# PANEL_A3_v4.net
KiCad netlist of a schematic drawn in Altium Designer
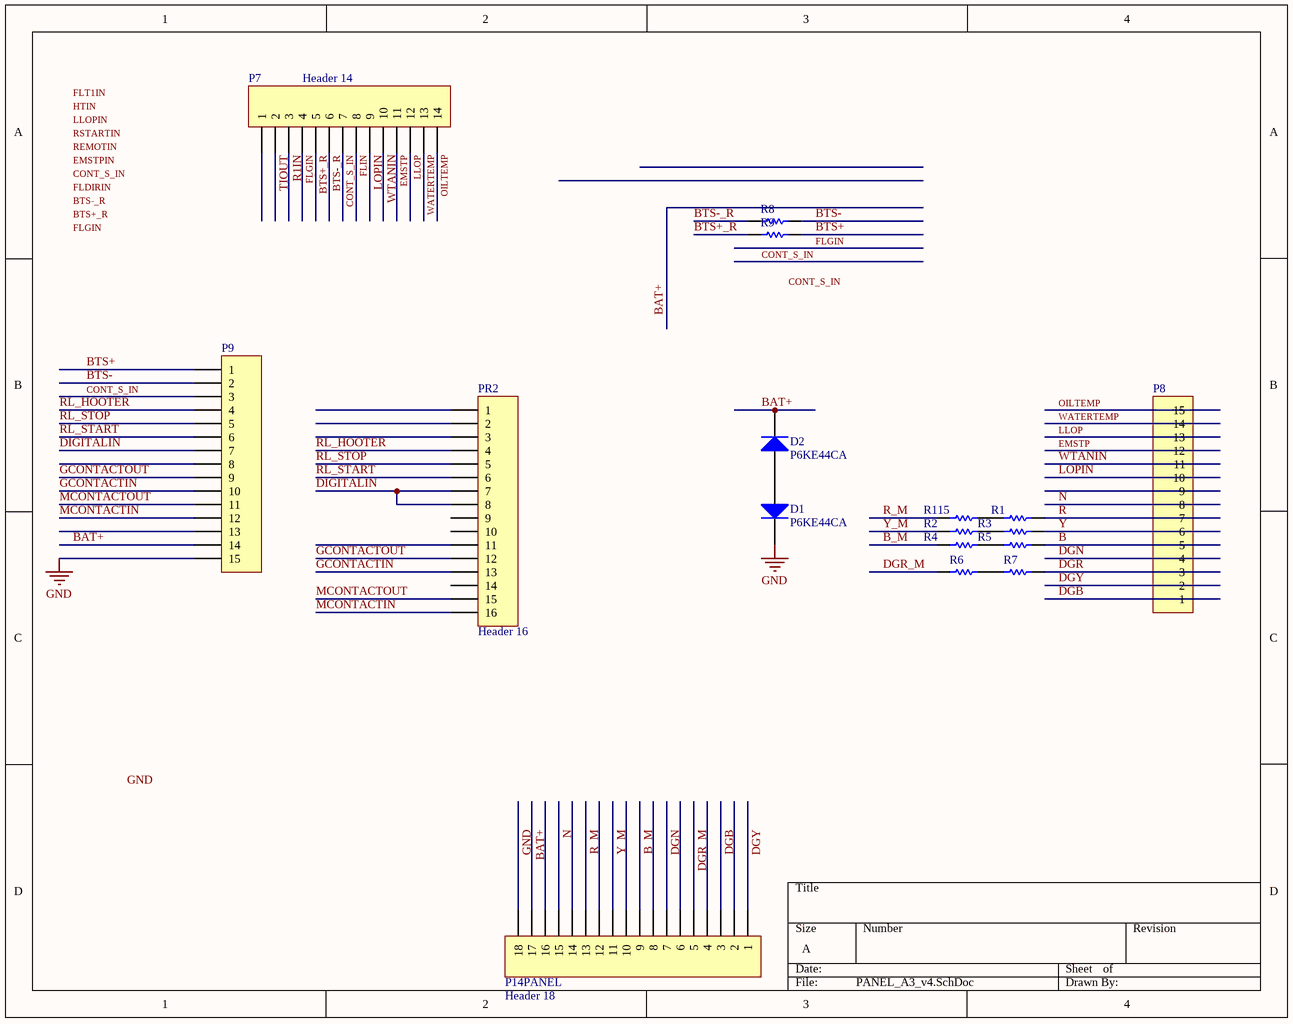
[diagram p0: PANEL_A3_v4.SchDoc]

(export (version "E")
  (design (tool "Eeschema 10.0.6"))
  (components
    (comp (ref "D1")
      (value "P6KE44CA")
      (footprint "DIODE1A")
      (description "3 Amp Medium Power Silicon Rectifier Diode")
      (fields (field (name "PUBLISHER") "Altium Limited"))
      (libsource (lib "Miscellaneous Devices") (part "Diode 1N5408"))
    )
    (comp (ref "D2")
      (value "P6KE44CA")
      (footprint "DIODE1A")
      (description "3 Amp Medium Power Silicon Rectifier Diode")
      (fields (field (name "PUBLISHER") "Altium Limited"))
      (libsource (lib "Miscellaneous Devices") (part "Diode 1N5408"))
    )
    (comp (ref "P7")
      (value "Header 14")
      (footprint "HDR1X14_BURGE_M")
      (description "Header, 14-Pin")
      (fields (field (name "PUBLISHER") "Altium Limited"))
      (libsource (lib "Miscellaneous Connectors") (part "Header 14"))
    )
    (comp (ref "P8")
      (value "XY2500 7PIN+8PIN MALE ST, FEMALE R/A")
      (footprint "XY2500_15PIN_M_ST")
      (description "Header, 15-Pin")
      (fields (field (name "PUBLISHER") "Altium Limited"))
      (libsource (lib "") (part "Header 15_1"))
    )
    (comp (ref "P9")
      (value "XY2500 7PIN+8PIN MALE ST, FEMALE R/A")
      (footprint "XY2500_15PIN_M_ST")
      (description "Header, 15-Pin")
      (fields (field (name "PUBLISHER") "Altium Limited"))
      (libsource (lib "Miscellaneous Connectors") (part "Header 15"))
    )
    (comp (ref "P14PANEL")
      (value "Header 18")
      (footprint "HDR1X18_BURGE_M")
      (description "Header, 18-Pin")
      (fields (field (name "PUBLISHER") "Altium Limited"))
      (libsource (lib "Miscellaneous Connectors") (part "Header 18"))
    )
    (comp (ref "PR2")
      (value "Header 16")
      (footprint "HDR1X16_BURGE_F")
      (description "Header, 16-Pin")
      (fields (field (name "PUBLISHER") "Altium Limited"))
      (libsource (lib "Miscellaneous Connectors") (part "Header 16"))
    )
    (comp (ref "R1")
      (value "MFR 1M .5W")
      (footprint "AXIAL-0.5")
      (description "Semiconductor Resistor")
      (fields (field (name "PUBLISHER") "Altium Limited"))
      (libsource (lib "Miscellaneous Devices") (part "Res Semi"))
    )
    (comp (ref "R2")
      (value "MFR 1M .5W")
      (footprint "AXIAL-0.5")
      (description "Semiconductor Resistor")
      (fields (field (name "PUBLISHER") "Altium Limited"))
      (libsource (lib "Miscellaneous Devices") (part "Res Semi"))
    )
    (comp (ref "R3")
      (value "MFR 1M .5W")
      (footprint "AXIAL-0.5")
      (description "Semiconductor Resistor")
      (fields (field (name "PUBLISHER") "Altium Limited"))
      (libsource (lib "Miscellaneous Devices") (part "Res Semi"))
    )
    (comp (ref "R4")
      (value "MFR 1M .5W")
      (footprint "AXIAL-0.5")
      (description "Semiconductor Resistor")
      (fields (field (name "PUBLISHER") "Altium Limited"))
      (libsource (lib "Miscellaneous Devices") (part "Res Semi"))
    )
    (comp (ref "R5")
      (value "MFR 1M .5W")
      (footprint "AXIAL-0.5")
      (description "Semiconductor Resistor")
      (fields (field (name "PUBLISHER") "Altium Limited"))
      (libsource (lib "Miscellaneous Devices") (part "Res Semi"))
    )
    (comp (ref "R6")
      (value "MFR 1M .5W")
      (footprint "AXIAL-0.5")
      (description "Semiconductor Resistor")
      (fields (field (name "PUBLISHER") "Altium Limited"))
      (libsource (lib "Miscellaneous Devices") (part "Res Semi"))
    )
    (comp (ref "R7")
      (value "MFR 1M .5W")
      (footprint "AXIAL-0.5")
      (description "Semiconductor Resistor")
      (fields (field (name "PUBLISHER") "Altium Limited"))
      (libsource (lib "Miscellaneous Devices") (part "Res Semi"))
    )
    (comp (ref "R8")
      (value "MFR 1M .5W")
      (footprint "AXIAL-0.5")
      (description "Semiconductor Resistor")
      (fields (field (name "PUBLISHER") "Altium Limited"))
      (libsource (lib "Miscellaneous Devices") (part "Res Semi"))
    )
    (comp (ref "R9")
      (value "MFR 1M .5W")
      (footprint "AXIAL-0.5")
      (description "Semiconductor Resistor")
      (fields (field (name "PUBLISHER") "Altium Limited"))
      (libsource (lib "Miscellaneous Devices") (part "Res Semi"))
    )
    (comp (ref "R115")
      (value "MFR 1M .5W")
      (footprint "AXIAL-0.5")
      (description "Semiconductor Resistor")
      (fields (field (name "PUBLISHER") "Altium Limited"))
      (libsource (lib "Miscellaneous Devices") (part "Res Semi"))
    )
  )
  (nets
    (net (code "1") (name "/B") (class "Default")
      (node (ref "P8") (pin "5") (pinfunction "5_5") (pintype "passive"))
      (node (ref "R5") (pin "2") (pinfunction "2_2") (pintype "passive"))
    )
    (net (code "2") (name "/BAT+") (class "Default")
      (node (ref "D2") (pin "2") (pinfunction "K_2") (pintype "passive"))
      (node (ref "P14PANEL") (pin "17") (pinfunction "17_17") (pintype "passive"))
      (node (ref "P9") (pin "14") (pinfunction "14_14") (pintype "passive"))
    )
    (net (code "3") (name "/BTS+") (class "Default")
      (node (ref "P9") (pin "1") (pinfunction "1_1") (pintype "passive"))
      (node (ref "R9") (pin "2") (pinfunction "2_2") (pintype "passive"))
    )
    (net (code "4") (name "/BTS+_R") (class "Default")
      (node (ref "P7") (pin "5") (pinfunction "5_5") (pintype "passive"))
      (node (ref "R9") (pin "1") (pinfunction "1_1") (pintype "passive"))
    )
    (net (code "5") (name "/BTS-") (class "Default")
      (node (ref "P9") (pin "2") (pinfunction "2_2") (pintype "passive"))
      (node (ref "R8") (pin "2") (pinfunction "2_2") (pintype "passive"))
    )
    (net (code "6") (name "/BTS-_R") (class "Default")
      (node (ref "P7") (pin "6") (pinfunction "6_6") (pintype "passive"))
      (node (ref "R8") (pin "1") (pinfunction "1_1") (pintype "passive"))
    )
    (net (code "7") (name "/B_M") (class "Default")
      (node (ref "P14PANEL") (pin "9") (pinfunction "9_9") (pintype "passive"))
      (node (ref "R4") (pin "1") (pinfunction "1_1") (pintype "passive"))
    )
    (net (code "8") (name "/CONT_S_IN") (class "Default")
      (node (ref "P7") (pin "7") (pinfunction "7_7") (pintype "passive"))
      (node (ref "P9") (pin "3") (pinfunction "3_3") (pintype "passive"))
    )
    (net (code "9") (name "/DGB") (class "Default")
      (node (ref "P14PANEL") (pin "3") (pinfunction "3_3") (pintype "passive"))
      (node (ref "P8") (pin "1") (pinfunction "1_1") (pintype "passive"))
    )
    (net (code "10") (name "/DGN") (class "Default")
      (node (ref "P14PANEL") (pin "7") (pinfunction "7_7") (pintype "passive"))
      (node (ref "P8") (pin "4") (pinfunction "4_4") (pintype "passive"))
    )
    (net (code "11") (name "/DGR") (class "Default")
      (node (ref "P8") (pin "3") (pinfunction "3_3") (pintype "passive"))
      (node (ref "R7") (pin "2") (pinfunction "2_2") (pintype "passive"))
    )
    (net (code "12") (name "/DGR_M") (class "Default")
      (node (ref "P14PANEL") (pin "5") (pinfunction "5_5") (pintype "passive"))
      (node (ref "R6") (pin "1") (pinfunction "1_1") (pintype "passive"))
    )
    (net (code "13") (name "/DGY") (class "Default")
      (node (ref "P14PANEL") (pin "1") (pinfunction "1_1") (pintype "passive"))
      (node (ref "P8") (pin "2") (pinfunction "2_2") (pintype "passive"))
    )
    (net (code "14") (name "/DIGITALIN") (class "Default")
      (node (ref "P9") (pin "7") (pinfunction "7_7") (pintype "passive"))
      (node (ref "PR2") (pin "7") (pinfunction "7_7") (pintype "passive"))
      (node (ref "PR2") (pin "8") (pinfunction "8_8") (pintype "passive"))
    )
    (net (code "15") (name "/EMSTP") (class "Default")
      (node (ref "P7") (pin "11") (pinfunction "11_11") (pintype "passive"))
      (node (ref "P8") (pin "12") (pinfunction "12_12") (pintype "passive"))
    )
    (net (code "18") (name "/FLGIN") (class "Default")
      (node (ref "P7") (pin "4") (pinfunction "4_4") (pintype "passive"))
    )
    (net (code "19") (name "/FLIN") (class "Default")
      (node (ref "P7") (pin "8") (pinfunction "8_8") (pintype "passive"))
    )
    (net (code "21") (name "/GCONTACTIN") (class "Default")
      (node (ref "P9") (pin "10") (pinfunction "10_10") (pintype "passive"))
      (node (ref "PR2") (pin "13") (pinfunction "13_13") (pintype "passive"))
    )
    (net (code "22") (name "/GCONTACTOUT") (class "Default")
      (node (ref "P9") (pin "9") (pinfunction "9_9") (pintype "passive"))
      (node (ref "PR2") (pin "12") (pinfunction "12_12") (pintype "passive"))
    )
    (net (code "24") (name "/LLOP") (class "Default")
      (node (ref "P7") (pin "12") (pinfunction "12_12") (pintype "passive"))
      (node (ref "P8") (pin "13") (pinfunction "13_13") (pintype "passive"))
    )
    (net (code "26") (name "/LOPIN") (class "Default")
      (node (ref "P7") (pin "9") (pinfunction "9_9") (pintype "passive"))
      (node (ref "P8") (pin "10") (pinfunction "10_10") (pintype "passive"))
    )
    (net (code "27") (name "/MCONTACTIN") (class "Default")
      (node (ref "P9") (pin "12") (pinfunction "12_12") (pintype "passive"))
      (node (ref "PR2") (pin "16") (pinfunction "16_16") (pintype "passive"))
    )
    (net (code "28") (name "/MCONTACTOUT") (class "Default")
      (node (ref "P9") (pin "11") (pinfunction "11_11") (pintype "passive"))
      (node (ref "PR2") (pin "15") (pinfunction "15_15") (pintype "passive"))
    )
    (net (code "29") (name "/N") (class "Default")
      (node (ref "P14PANEL") (pin "15") (pinfunction "15_15") (pintype "passive"))
      (node (ref "P8") (pin "8") (pinfunction "8_8") (pintype "passive"))
    )
    (net (code "30") (name "/OILTEMP") (class "Default")
      (node (ref "P7") (pin "14") (pinfunction "14_14") (pintype "passive"))
      (node (ref "P8") (pin "15") (pinfunction "15_15") (pintype "passive"))
    )
    (net (code "31") (name "/R") (class "Default")
      (node (ref "P8") (pin "7") (pinfunction "7_7") (pintype "passive"))
      (node (ref "R1") (pin "2") (pinfunction "2_2") (pintype "passive"))
    )
    (net (code "32") (name "/R1IN") (class "Default")
      (node (ref "P7") (pin "3") (pinfunction "3_3") (pintype "passive"))
    )
    (net (code "34") (name "/RL_HOOTER") (class "Default")
      (node (ref "P9") (pin "4") (pinfunction "4_4") (pintype "passive"))
      (node (ref "PR2") (pin "4") (pinfunction "4_4") (pintype "passive"))
    )
    (net (code "35") (name "/RL_START") (class "Default")
      (node (ref "P9") (pin "6") (pinfunction "6_6") (pintype "passive"))
      (node (ref "PR2") (pin "6") (pinfunction "6_6") (pintype "passive"))
    )
    (net (code "36") (name "/RL_STOP") (class "Default")
      (node (ref "P9") (pin "5") (pinfunction "5_5") (pintype "passive"))
      (node (ref "PR2") (pin "5") (pinfunction "5_5") (pintype "passive"))
    )
    (net (code "38") (name "/R_M") (class "Default")
      (node (ref "P14PANEL") (pin "13") (pinfunction "13_13") (pintype "passive"))
      (node (ref "R115") (pin "1") (pinfunction "1_1") (pintype "passive"))
    )
    (net (code "39") (name "/TIOUT") (class "Default")
      (node (ref "P7") (pin "2") (pinfunction "2_2") (pintype "passive"))
    )
    (net (code "40") (name "/WATERTEMP") (class "Default")
      (node (ref "P7") (pin "13") (pinfunction "13_13") (pintype "passive"))
      (node (ref "P8") (pin "14") (pinfunction "14_14") (pintype "passive"))
    )
    (net (code "41") (name "/WTANIN") (class "Default")
      (node (ref "P7") (pin "10") (pinfunction "10_10") (pintype "passive"))
      (node (ref "P8") (pin "11") (pinfunction "11_11") (pintype "passive"))
    )
    (net (code "42") (name "/Y") (class "Default")
      (node (ref "P8") (pin "6") (pinfunction "6_6") (pintype "passive"))
      (node (ref "R3") (pin "2") (pinfunction "2_2") (pintype "passive"))
    )
    (net (code "43") (name "/Y_M") (class "Default")
      (node (ref "P14PANEL") (pin "11") (pinfunction "11_11") (pintype "passive"))
      (node (ref "R2") (pin "1") (pinfunction "1_1") (pintype "passive"))
    )
    (net (code "44") (name "GND") (class "Default")
      (node (ref "D1") (pin "2") (pinfunction "K_2") (pintype "passive"))
      (node (ref "P14PANEL") (pin "18") (pinfunction "18_18") (pintype "passive"))
      (node (ref "P9") (pin "15") (pinfunction "15_15") (pintype "passive"))
    )
    (net (code "45") (name "Net-(D1-A)") (class "Default")
      (node (ref "D1") (pin "1") (pinfunction "A_1") (pintype "passive"))
      (node (ref "D2") (pin "1") (pinfunction "A_1") (pintype "passive"))
    )
    (net (code "46") (name "Net-(R1-Pad1)") (class "Default")
      (node (ref "R1") (pin "1") (pinfunction "1_1") (pintype "passive"))
      (node (ref "R115") (pin "2") (pinfunction "2_2") (pintype "passive"))
    )
    (net (code "47") (name "Net-(R2-Pad2)") (class "Default")
      (node (ref "R2") (pin "2") (pinfunction "2_2") (pintype "passive"))
      (node (ref "R3") (pin "1") (pinfunction "1_1") (pintype "passive"))
    )
    (net (code "48") (name "Net-(R4-Pad2)") (class "Default")
      (node (ref "R4") (pin "2") (pinfunction "2_2") (pintype "passive"))
      (node (ref "R5") (pin "1") (pinfunction "1_1") (pintype "passive"))
    )
    (net (code "49") (name "Net-(R6-Pad2)") (class "Default")
      (node (ref "R6") (pin "2") (pinfunction "2_2") (pintype "passive"))
      (node (ref "R7") (pin "1") (pinfunction "1_1") (pintype "passive"))
    )
    (net (code "50") (name "unconnected-(P7-Pad1)") (class "Default")
      (node (ref "P7") (pin "1") (pinfunction "1_1") (pintype "passive"))
    )
    (net (code "51") (name "unconnected-(P8-Pad9)") (class "Default")
      (node (ref "P8") (pin "9") (pinfunction "9_9") (pintype "passive"))
    )
    (net (code "52") (name "unconnected-(P9-Pad8)") (class "Default")
      (node (ref "P9") (pin "8") (pinfunction "8_8") (pintype "passive"))
    )
    (net (code "53") (name "unconnected-(P9-Pad13)") (class "Default")
      (node (ref "P9") (pin "13") (pinfunction "13_13") (pintype "passive"))
    )
    (net (code "54") (name "unconnected-(P14PANEL-Pad2)") (class "Default")
      (node (ref "P14PANEL") (pin "2") (pinfunction "2_2") (pintype "passive"))
    )
    (net (code "55") (name "unconnected-(P14PANEL-Pad4)") (class "Default")
      (node (ref "P14PANEL") (pin "4") (pinfunction "4_4") (pintype "passive"))
    )
    (net (code "56") (name "unconnected-(P14PANEL-Pad6)") (class "Default")
      (node (ref "P14PANEL") (pin "6") (pinfunction "6_6") (pintype "passive"))
    )
    (net (code "57") (name "unconnected-(P14PANEL-Pad8)") (class "Default")
      (node (ref "P14PANEL") (pin "8") (pinfunction "8_8") (pintype "passive"))
    )
    (net (code "58") (name "unconnected-(P14PANEL-Pad10)") (class "Default")
      (node (ref "P14PANEL") (pin "10") (pinfunction "10_10") (pintype "passive"))
    )
    (net (code "59") (name "unconnected-(P14PANEL-Pad12)") (class "Default")
      (node (ref "P14PANEL") (pin "12") (pinfunction "12_12") (pintype "passive"))
    )
    (net (code "60") (name "unconnected-(P14PANEL-Pad14)") (class "Default")
      (node (ref "P14PANEL") (pin "14") (pinfunction "14_14") (pintype "passive"))
    )
    (net (code "61") (name "unconnected-(P14PANEL-Pad16)") (class "Default")
      (node (ref "P14PANEL") (pin "16") (pinfunction "16_16") (pintype "passive"))
    )
    (net (code "62") (name "unconnected-(PR2-Pad1)") (class "Default")
      (node (ref "PR2") (pin "1") (pinfunction "1_1") (pintype "passive"))
    )
    (net (code "63") (name "unconnected-(PR2-Pad2)") (class "Default")
      (node (ref "PR2") (pin "2") (pinfunction "2_2") (pintype "passive"))
    )
    (net (code "64") (name "unconnected-(PR2-Pad3)") (class "Default")
      (node (ref "PR2") (pin "3") (pinfunction "3_3") (pintype "passive"))
    )
    (net (code "65") (name "unconnected-(PR2-Pad9)") (class "Default")
      (node (ref "PR2") (pin "9") (pinfunction "9_9") (pintype "passive"))
    )
    (net (code "66") (name "unconnected-(PR2-Pad10)") (class "Default")
      (node (ref "PR2") (pin "10") (pinfunction "10_10") (pintype "passive"))
    )
    (net (code "67") (name "unconnected-(PR2-Pad11)") (class "Default")
      (node (ref "PR2") (pin "11") (pinfunction "11_11") (pintype "passive"))
    )
    (net (code "68") (name "unconnected-(PR2-Pad14)") (class "Default")
      (node (ref "PR2") (pin "14") (pinfunction "14_14") (pintype "passive"))
    )
  )
)
